# smd-reflow-1.net
KiCad netlist of a schematic drawn in EAGLE
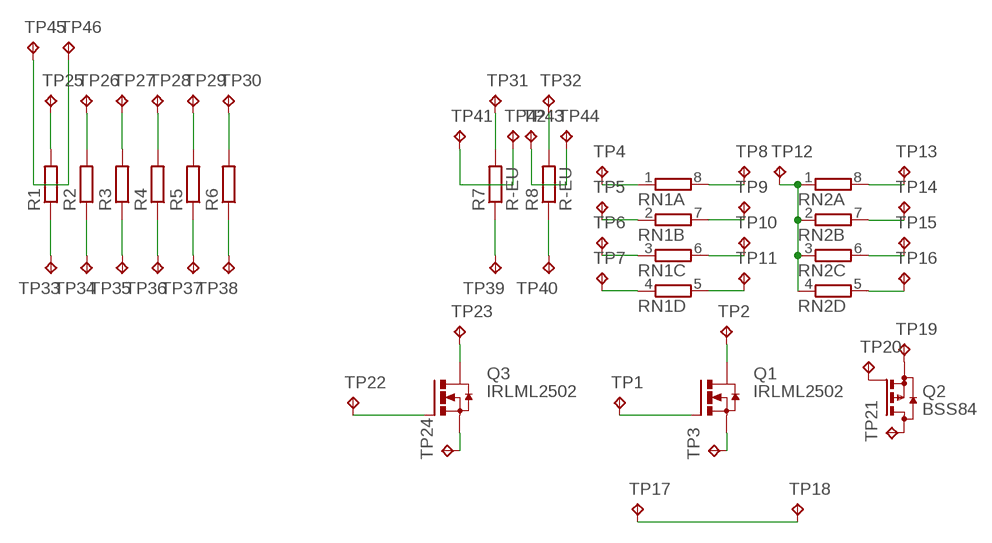
[diagram p0: schematic, sheet 1]

(export (version "E")
  (design (tool "Eeschema 10.0.6"))
  (components
    (comp (ref "Q1")
      (value "IRLML2502")
      (footprint "eagle-import:MICRO3")
      (libsource (lib "eagle-import") (part "IRLML2502"))
    )
    (comp (ref "Q2")
      (value "BSS84")
      (footprint "eagle-import:SOT23")
      (libsource (lib "eagle-import") (part "BSS84"))
    )
    (comp (ref "Q3")
      (value "IRLML2502")
      (footprint "eagle-import:MICRO3")
      (libsource (lib "eagle-import") (part "IRLML2502"))
    )
    (comp (ref "R1")
      (value "R-EU_R0603")
      (footprint "eagle-import:R0603")
      (libsource (lib "eagle-import") (part "R-EU_R0603"))
    )
    (comp (ref "R2")
      (value "R-EU_R0603")
      (footprint "eagle-import:R0603")
      (libsource (lib "eagle-import") (part "R-EU_R0603"))
    )
    (comp (ref "R3")
      (value "R-EU_R0805")
      (footprint "eagle-import:R0805")
      (libsource (lib "eagle-import") (part "R-EU_R0805"))
    )
    (comp (ref "R4")
      (value "R-EU_R0805")
      (footprint "eagle-import:R0805")
      (libsource (lib "eagle-import") (part "R-EU_R0805"))
    )
    (comp (ref "R5")
      (value "R-EU_R0805W")
      (footprint "eagle-import:R0805W")
      (libsource (lib "eagle-import") (part "R-EU_R0805W"))
    )
    (comp (ref "R6")
      (value "R-EU_R0805W")
      (footprint "eagle-import:R0805W")
      (libsource (lib "eagle-import") (part "R-EU_R0805W"))
    )
    (comp (ref "R7")
      (value "R-EU")
      (footprint "eagle-import:R0805H")
      (libsource (lib "eagle-import") (part "R-EU"))
    )
    (comp (ref "R8")
      (value "R-EU")
      (footprint "eagle-import:R0805H")
      (libsource (lib "eagle-import") (part "R-EU"))
    )
    (comp (ref "RN1")
      (value "4R-NEXB38V")
      (footprint "eagle-import:EXB38V")
      (libsource (lib "eagle-import") (part "4R-NEXB38V"))
    )
    (comp (ref "RN2")
      (value "4R-NEXB38V")
      (footprint "eagle-import:EXB38V")
      (libsource (lib "eagle-import") (part "4R-NEXB38V"))
    )
    (comp (ref "TP1")
      (value "TPB1,27")
      (footprint "eagle-import:B1,27")
      (libsource (lib "eagle-import") (part "TPB1,27"))
    )
    (comp (ref "TP2")
      (value "TPB1,27")
      (footprint "eagle-import:B1,27")
      (libsource (lib "eagle-import") (part "TPB1,27"))
    )
    (comp (ref "TP3")
      (value "TPB1,27")
      (footprint "eagle-import:B1,27")
      (libsource (lib "eagle-import") (part "TPB1,27"))
    )
    (comp (ref "TP4")
      (value "TPB1,27")
      (footprint "eagle-import:B1,27")
      (libsource (lib "eagle-import") (part "TPB1,27"))
    )
    (comp (ref "TP5")
      (value "TPB1,27")
      (footprint "eagle-import:B1,27")
      (libsource (lib "eagle-import") (part "TPB1,27"))
    )
    (comp (ref "TP6")
      (value "TPB1,27")
      (footprint "eagle-import:B1,27")
      (libsource (lib "eagle-import") (part "TPB1,27"))
    )
    (comp (ref "TP7")
      (value "TPB1,27")
      (footprint "eagle-import:B1,27")
      (libsource (lib "eagle-import") (part "TPB1,27"))
    )
    (comp (ref "TP8")
      (value "TPB1,27")
      (footprint "eagle-import:B1,27")
      (libsource (lib "eagle-import") (part "TPB1,27"))
    )
    (comp (ref "TP9")
      (value "TPB1,27")
      (footprint "eagle-import:B1,27")
      (libsource (lib "eagle-import") (part "TPB1,27"))
    )
    (comp (ref "TP10")
      (value "TPB1,27")
      (footprint "eagle-import:B1,27")
      (libsource (lib "eagle-import") (part "TPB1,27"))
    )
    (comp (ref "TP11")
      (value "TPB1,27")
      (footprint "eagle-import:B1,27")
      (libsource (lib "eagle-import") (part "TPB1,27"))
    )
    (comp (ref "TP12")
      (value "TPB1,27")
      (footprint "eagle-import:B1,27")
      (libsource (lib "eagle-import") (part "TPB1,27"))
    )
    (comp (ref "TP13")
      (value "TPB1,27")
      (footprint "eagle-import:B1,27")
      (libsource (lib "eagle-import") (part "TPB1,27"))
    )
    (comp (ref "TP14")
      (value "TPB1,27")
      (footprint "eagle-import:B1,27")
      (libsource (lib "eagle-import") (part "TPB1,27"))
    )
    (comp (ref "TP15")
      (value "TPB1,27")
      (footprint "eagle-import:B1,27")
      (libsource (lib "eagle-import") (part "TPB1,27"))
    )
    (comp (ref "TP16")
      (value "TPB1,27")
      (footprint "eagle-import:B1,27")
      (libsource (lib "eagle-import") (part "TPB1,27"))
    )
    (comp (ref "TP17")
      (value "TPB1,27")
      (footprint "eagle-import:B1,27")
      (libsource (lib "eagle-import") (part "TPB1,27"))
    )
    (comp (ref "TP18")
      (value "TPB1,27")
      (footprint "eagle-import:B1,27")
      (libsource (lib "eagle-import") (part "TPB1,27"))
    )
    (comp (ref "TP19")
      (value "TPB1,27")
      (footprint "eagle-import:B1,27")
      (libsource (lib "eagle-import") (part "TPB1,27"))
    )
    (comp (ref "TP20")
      (value "TPB1,27")
      (footprint "eagle-import:B1,27")
      (libsource (lib "eagle-import") (part "TPB1,27"))
    )
    (comp (ref "TP21")
      (value "TPB1,27")
      (footprint "eagle-import:B1,27")
      (libsource (lib "eagle-import") (part "TPB1,27"))
    )
    (comp (ref "TP22")
      (value "TPB1,27")
      (footprint "eagle-import:B1,27")
      (libsource (lib "eagle-import") (part "TPB1,27"))
    )
    (comp (ref "TP23")
      (value "TPB1,27")
      (footprint "eagle-import:B1,27")
      (libsource (lib "eagle-import") (part "TPB1,27"))
    )
    (comp (ref "TP24")
      (value "TPB1,27")
      (footprint "eagle-import:B1,27")
      (libsource (lib "eagle-import") (part "TPB1,27"))
    )
    (comp (ref "TP25")
      (value "TPB1,27")
      (footprint "eagle-import:B1,27")
      (libsource (lib "eagle-import") (part "TPB1,27"))
    )
    (comp (ref "TP26")
      (value "TPB1,27")
      (footprint "eagle-import:B1,27")
      (libsource (lib "eagle-import") (part "TPB1,27"))
    )
    (comp (ref "TP27")
      (value "TPB1,27")
      (footprint "eagle-import:B1,27")
      (libsource (lib "eagle-import") (part "TPB1,27"))
    )
    (comp (ref "TP28")
      (value "TPB1,27")
      (footprint "eagle-import:B1,27")
      (libsource (lib "eagle-import") (part "TPB1,27"))
    )
    (comp (ref "TP29")
      (value "TPB1,27")
      (footprint "eagle-import:B1,27")
      (libsource (lib "eagle-import") (part "TPB1,27"))
    )
    (comp (ref "TP30")
      (value "TPB1,27")
      (footprint "eagle-import:B1,27")
      (libsource (lib "eagle-import") (part "TPB1,27"))
    )
    (comp (ref "TP31")
      (value "TPB1,27")
      (footprint "eagle-import:B1,27")
      (libsource (lib "eagle-import") (part "TPB1,27"))
    )
    (comp (ref "TP32")
      (value "TPB1,27")
      (footprint "eagle-import:B1,27")
      (libsource (lib "eagle-import") (part "TPB1,27"))
    )
    (comp (ref "TP33")
      (value "TPB1,27")
      (footprint "eagle-import:B1,27")
      (libsource (lib "eagle-import") (part "TPB1,27"))
    )
    (comp (ref "TP34")
      (value "TPB1,27")
      (footprint "eagle-import:B1,27")
      (libsource (lib "eagle-import") (part "TPB1,27"))
    )
    (comp (ref "TP35")
      (value "TPB1,27")
      (footprint "eagle-import:B1,27")
      (libsource (lib "eagle-import") (part "TPB1,27"))
    )
    (comp (ref "TP36")
      (value "TPB1,27")
      (footprint "eagle-import:B1,27")
      (libsource (lib "eagle-import") (part "TPB1,27"))
    )
    (comp (ref "TP37")
      (value "TPB1,27")
      (footprint "eagle-import:B1,27")
      (libsource (lib "eagle-import") (part "TPB1,27"))
    )
    (comp (ref "TP38")
      (value "TPB1,27")
      (footprint "eagle-import:B1,27")
      (libsource (lib "eagle-import") (part "TPB1,27"))
    )
    (comp (ref "TP39")
      (value "TPB1,27")
      (footprint "eagle-import:B1,27")
      (libsource (lib "eagle-import") (part "TPB1,27"))
    )
    (comp (ref "TP40")
      (value "TPB1,27")
      (footprint "eagle-import:B1,27")
      (libsource (lib "eagle-import") (part "TPB1,27"))
    )
    (comp (ref "TP41")
      (value "TPB1,27")
      (footprint "eagle-import:B1,27")
      (libsource (lib "eagle-import") (part "TPB1,27"))
    )
    (comp (ref "TP42")
      (value "TPB1,27")
      (footprint "eagle-import:B1,27")
      (libsource (lib "eagle-import") (part "TPB1,27"))
    )
    (comp (ref "TP43")
      (value "TPB1,27")
      (footprint "eagle-import:B1,27")
      (libsource (lib "eagle-import") (part "TPB1,27"))
    )
    (comp (ref "TP44")
      (value "TPB1,27")
      (footprint "eagle-import:B1,27")
      (libsource (lib "eagle-import") (part "TPB1,27"))
    )
    (comp (ref "TP45")
      (value "TPB1,27")
      (footprint "eagle-import:B1,27")
      (libsource (lib "eagle-import") (part "TPB1,27"))
    )
    (comp (ref "TP46")
      (value "TPB1,27")
      (footprint "eagle-import:B1,27")
      (libsource (lib "eagle-import") (part "TPB1,27"))
    )
  )
  (nets
    (net (code "1") (name "Net-(Q1-D)") (class "Default")
      (node (ref "Q1") (pin "3") (pinfunction "D_3") (pintype "passive"))
      (node (ref "TP2") (pin "TP") (pinfunction "TP_TP") (pintype "input"))
    )
    (net (code "2") (name "Net-(Q1-G)") (class "Default")
      (node (ref "Q1") (pin "1") (pinfunction "G_1") (pintype "passive"))
      (node (ref "TP1") (pin "TP") (pinfunction "TP_TP") (pintype "input"))
    )
    (net (code "3") (name "Net-(Q1-S)") (class "Default")
      (node (ref "Q1") (pin "2") (pinfunction "S_2") (pintype "passive"))
      (node (ref "TP3") (pin "TP") (pinfunction "TP_TP") (pintype "input"))
    )
    (net (code "4") (name "Net-(Q2-D)") (class "Default")
      (node (ref "Q2") (pin "3") (pinfunction "D_3") (pintype "passive"))
      (node (ref "TP21") (pin "TP") (pinfunction "TP_TP") (pintype "input"))
    )
    (net (code "5") (name "Net-(Q2-G)") (class "Default")
      (node (ref "Q2") (pin "1") (pinfunction "G_1") (pintype "passive"))
      (node (ref "TP20") (pin "TP") (pinfunction "TP_TP") (pintype "input"))
    )
    (net (code "6") (name "Net-(Q2-S)") (class "Default")
      (node (ref "Q2") (pin "2") (pinfunction "S_2") (pintype "passive"))
      (node (ref "TP19") (pin "TP") (pinfunction "TP_TP") (pintype "input"))
    )
    (net (code "7") (name "Net-(Q3-D)") (class "Default")
      (node (ref "Q3") (pin "3") (pinfunction "D_3") (pintype "passive"))
      (node (ref "TP23") (pin "TP") (pinfunction "TP_TP") (pintype "input"))
    )
    (net (code "8") (name "Net-(Q3-G)") (class "Default")
      (node (ref "Q3") (pin "1") (pinfunction "G_1") (pintype "passive"))
      (node (ref "TP22") (pin "TP") (pinfunction "TP_TP") (pintype "input"))
    )
    (net (code "9") (name "Net-(Q3-S)") (class "Default")
      (node (ref "Q3") (pin "2") (pinfunction "S_2") (pintype "passive"))
      (node (ref "TP24") (pin "TP") (pinfunction "TP_TP") (pintype "input"))
    )
    (net (code "10") (name "Net-(R1-Pad1)") (class "Default")
      (node (ref "R1") (pin "1") (pinfunction "1_1") (pintype "passive"))
      (node (ref "TP33") (pin "TP") (pinfunction "TP_TP") (pintype "input"))
    )
    (net (code "11") (name "Net-(R1-Pad2)") (class "Default")
      (node (ref "R1") (pin "2") (pinfunction "2_2") (pintype "passive"))
      (node (ref "TP25") (pin "TP") (pinfunction "TP_TP") (pintype "input"))
    )
    (net (code "12") (name "Net-(R2-Pad1)") (class "Default")
      (node (ref "R2") (pin "1") (pinfunction "1_1") (pintype "passive"))
      (node (ref "TP34") (pin "TP") (pinfunction "TP_TP") (pintype "input"))
    )
    (net (code "13") (name "Net-(R2-Pad2)") (class "Default")
      (node (ref "R2") (pin "2") (pinfunction "2_2") (pintype "passive"))
      (node (ref "TP26") (pin "TP") (pinfunction "TP_TP") (pintype "input"))
    )
    (net (code "14") (name "Net-(R3-Pad1)") (class "Default")
      (node (ref "R3") (pin "1") (pinfunction "1_1") (pintype "passive"))
      (node (ref "TP35") (pin "TP") (pinfunction "TP_TP") (pintype "input"))
    )
    (net (code "15") (name "Net-(R3-Pad2)") (class "Default")
      (node (ref "R3") (pin "2") (pinfunction "2_2") (pintype "passive"))
      (node (ref "TP27") (pin "TP") (pinfunction "TP_TP") (pintype "input"))
    )
    (net (code "16") (name "Net-(R4-Pad1)") (class "Default")
      (node (ref "R4") (pin "1") (pinfunction "1_1") (pintype "passive"))
      (node (ref "TP36") (pin "TP") (pinfunction "TP_TP") (pintype "input"))
    )
    (net (code "17") (name "Net-(R4-Pad2)") (class "Default")
      (node (ref "R4") (pin "2") (pinfunction "2_2") (pintype "passive"))
      (node (ref "TP28") (pin "TP") (pinfunction "TP_TP") (pintype "input"))
    )
    (net (code "18") (name "Net-(R5-Pad1)") (class "Default")
      (node (ref "R5") (pin "1") (pinfunction "1_1") (pintype "passive"))
      (node (ref "TP37") (pin "TP") (pinfunction "TP_TP") (pintype "input"))
    )
    (net (code "19") (name "Net-(R5-Pad2)") (class "Default")
      (node (ref "R5") (pin "2") (pinfunction "2_2") (pintype "passive"))
      (node (ref "TP29") (pin "TP") (pinfunction "TP_TP") (pintype "input"))
    )
    (net (code "20") (name "Net-(R6-Pad1)") (class "Default")
      (node (ref "R6") (pin "1") (pinfunction "1_1") (pintype "passive"))
      (node (ref "TP38") (pin "TP") (pinfunction "TP_TP") (pintype "input"))
    )
    (net (code "21") (name "Net-(R6-Pad2)") (class "Default")
      (node (ref "R6") (pin "2") (pinfunction "2_2") (pintype "passive"))
      (node (ref "TP30") (pin "TP") (pinfunction "TP_TP") (pintype "input"))
    )
    (net (code "22") (name "Net-(R7-Pad1)") (class "Default")
      (node (ref "R7") (pin "1") (pinfunction "1_1") (pintype "passive"))
      (node (ref "TP39") (pin "TP") (pinfunction "TP_TP") (pintype "input"))
    )
    (net (code "23") (name "Net-(R7-Pad2)") (class "Default")
      (node (ref "R7") (pin "2") (pinfunction "2_2") (pintype "passive"))
      (node (ref "TP31") (pin "TP") (pinfunction "TP_TP") (pintype "input"))
    )
    (net (code "24") (name "Net-(R8-Pad1)") (class "Default")
      (node (ref "R8") (pin "1") (pinfunction "1_1") (pintype "passive"))
      (node (ref "TP40") (pin "TP") (pinfunction "TP_TP") (pintype "input"))
    )
    (net (code "25") (name "Net-(R8-Pad2)") (class "Default")
      (node (ref "R8") (pin "2") (pinfunction "2_2") (pintype "passive"))
      (node (ref "TP32") (pin "TP") (pinfunction "TP_TP") (pintype "input"))
    )
    (net (code "26") (name "Net-(RN1-Pad1)") (class "Default")
      (node (ref "RN1") (pin "1") (pinfunction "1_1") (pintype "passive"))
      (node (ref "TP4") (pin "TP") (pinfunction "TP_TP") (pintype "input"))
    )
    (net (code "27") (name "Net-(RN1A-2)") (class "Default")
      (node (ref "RN1") (pin "8") (pinfunction "2_8") (pintype "passive"))
      (node (ref "TP8") (pin "TP") (pinfunction "TP_TP") (pintype "input"))
    )
    (net (code "28") (name "Net-(RN1B-1)") (class "Default")
      (node (ref "RN1") (pin "2") (pinfunction "1_2") (pintype "passive"))
      (node (ref "TP5") (pin "TP") (pinfunction "TP_TP") (pintype "input"))
    )
    (net (code "29") (name "Net-(RN1B-2)") (class "Default")
      (node (ref "RN1") (pin "7") (pinfunction "2_7") (pintype "passive"))
      (node (ref "TP9") (pin "TP") (pinfunction "TP_TP") (pintype "input"))
    )
    (net (code "30") (name "Net-(RN1C-1)") (class "Default")
      (node (ref "RN1") (pin "3") (pinfunction "1_3") (pintype "passive"))
      (node (ref "TP6") (pin "TP") (pinfunction "TP_TP") (pintype "input"))
    )
    (net (code "31") (name "Net-(RN1C-2)") (class "Default")
      (node (ref "RN1") (pin "6") (pinfunction "2_6") (pintype "passive"))
      (node (ref "TP10") (pin "TP") (pinfunction "TP_TP") (pintype "input"))
    )
    (net (code "32") (name "Net-(RN1D-1)") (class "Default")
      (node (ref "RN1") (pin "4") (pinfunction "1_4") (pintype "passive"))
      (node (ref "TP7") (pin "TP") (pinfunction "TP_TP") (pintype "input"))
    )
    (net (code "33") (name "Net-(RN1D-2)") (class "Default")
      (node (ref "RN1") (pin "5") (pinfunction "2_5") (pintype "passive"))
      (node (ref "TP11") (pin "TP") (pinfunction "TP_TP") (pintype "input"))
    )
    (net (code "34") (name "Net-(RN2A-2)") (class "Default")
      (node (ref "RN2") (pin "8") (pinfunction "2_8") (pintype "passive"))
      (node (ref "TP13") (pin "TP") (pinfunction "TP_TP") (pintype "input"))
    )
    (net (code "35") (name "Net-(RN2B-1)") (class "Default")
      (node (ref "RN2") (pin "1") (pinfunction "1_1") (pintype "passive"))
      (node (ref "RN2") (pin "2") (pinfunction "1_2") (pintype "passive"))
      (node (ref "RN2") (pin "3") (pinfunction "1_3") (pintype "passive"))
      (node (ref "RN2") (pin "4") (pinfunction "1_4") (pintype "passive"))
      (node (ref "TP12") (pin "TP") (pinfunction "TP_TP") (pintype "input"))
    )
    (net (code "36") (name "Net-(RN2B-2)") (class "Default")
      (node (ref "RN2") (pin "7") (pinfunction "2_7") (pintype "passive"))
      (node (ref "TP14") (pin "TP") (pinfunction "TP_TP") (pintype "input"))
    )
    (net (code "37") (name "Net-(RN2C-2)") (class "Default")
      (node (ref "RN2") (pin "6") (pinfunction "2_6") (pintype "passive"))
      (node (ref "TP15") (pin "TP") (pinfunction "TP_TP") (pintype "input"))
    )
    (net (code "38") (name "Net-(RN2D-2)") (class "Default")
      (node (ref "RN2") (pin "5") (pinfunction "2_5") (pintype "passive"))
      (node (ref "TP16") (pin "TP") (pinfunction "TP_TP") (pintype "input"))
    )
    (net (code "39") (name "Net-(TP17-PadTP)") (class "Default")
      (node (ref "TP17") (pin "TP") (pinfunction "TP_TP") (pintype "input"))
      (node (ref "TP18") (pin "TP") (pinfunction "TP_TP") (pintype "input"))
    )
    (net (code "40") (name "Net-(TP41-PadTP)") (class "Default")
      (node (ref "TP41") (pin "TP") (pinfunction "TP_TP") (pintype "input"))
      (node (ref "TP42") (pin "TP") (pinfunction "TP_TP") (pintype "input"))
    )
    (net (code "41") (name "Net-(TP43-PadTP)") (class "Default")
      (node (ref "TP43") (pin "TP") (pinfunction "TP_TP") (pintype "input"))
      (node (ref "TP44") (pin "TP") (pinfunction "TP_TP") (pintype "input"))
    )
    (net (code "42") (name "Net-(TP45-PadTP)") (class "Default")
      (node (ref "TP45") (pin "TP") (pinfunction "TP_TP") (pintype "input"))
      (node (ref "TP46") (pin "TP") (pinfunction "TP_TP") (pintype "input"))
    )
  )
)
